# motor_drive_basic.net
KiCad netlist of a schematic drawn in EAGLE
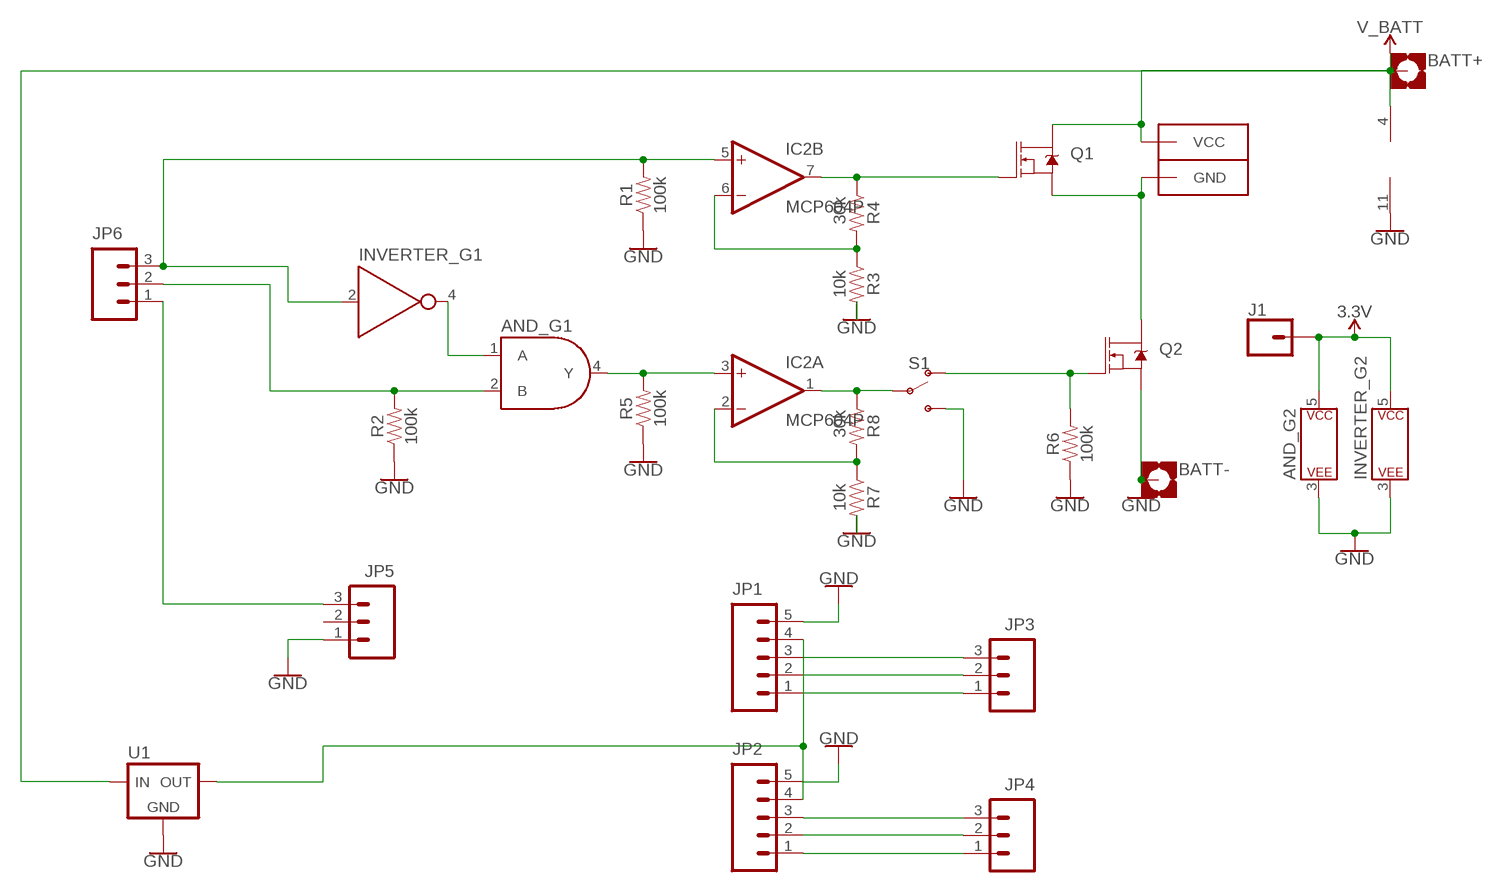
[diagram p0: schematic, sheet 1]

(export (version "E")
  (design (tool "Eeschema 10.0.6"))
  (components
    (comp (ref "AND_")
      (value "74LVC08SE")
      (footprint "eagle-import:SOT23-5")
      (libsource (lib "eagle-import") (part "7408SELVC"))
    )
    (comp (ref "BATT+")
      (value "MOUNT-PAD-SQUARE3.0")
      (footprint "eagle-import:3,0-PAD-SQUARE")
      (libsource (lib "eagle-import") (part "MOUNT-PAD-SQUARE3.0"))
    )
    (comp (ref "BATT-")
      (value "MOUNT-PAD-SQUARE3.0")
      (footprint "eagle-import:3,0-PAD-SQUARE")
      (libsource (lib "eagle-import") (part "MOUNT-PAD-SQUARE3.0"))
    )
    (comp (ref "CONN1")
      (value "ANDERSON_PP_DOUBLEVERTICAL")
      (footprint "eagle-import:ANDERSON_PP_DOUB_VERT")
      (libsource (lib "eagle-import") (part "ANDERSON_PP_DOUBLEVERTICAL"))
    )
    (comp (ref "IC2")
      (value "MCP604P")
      (footprint "eagle-import:DIL14")
      (libsource (lib "eagle-import") (part "MCP604P"))
    )
    (comp (ref "INVERTER_")
      (value "74HC1G04")
      (footprint "eagle-import:SOT353")
      (libsource (lib "eagle-import") (part "741G04HC"))
    )
    (comp (ref "J1")
      (value "CONN_01")
      (footprint "eagle-import:1X01")
      (libsource (lib "eagle-import") (part "CONN_01"))
    )
    (comp (ref "JP1")
      (value "M05PTH")
      (footprint "eagle-import:1X05")
      (libsource (lib "eagle-import") (part "M05PTH"))
    )
    (comp (ref "JP2")
      (value "M05PTH")
      (footprint "eagle-import:1X05")
      (libsource (lib "eagle-import") (part "M05PTH"))
    )
    (comp (ref "JP3")
      (value "M03PTH")
      (footprint "eagle-import:1X03")
      (libsource (lib "eagle-import") (part "M03PTH"))
    )
    (comp (ref "JP4")
      (value "M03PTH")
      (footprint "eagle-import:1X03")
      (libsource (lib "eagle-import") (part "M03PTH"))
    )
    (comp (ref "JP5")
      (value "M03PTH")
      (footprint "eagle-import:1X03")
      (libsource (lib "eagle-import") (part "M03PTH"))
    )
    (comp (ref "JP6")
      (value "M03PTH")
      (footprint "eagle-import:1X03")
      (libsource (lib "eagle-import") (part "M03PTH"))
    )
    (comp (ref "Q1")
      (value "MOSFET-NCH-FQP30N06L")
      (footprint "eagle-import:TO220V")
      (libsource (lib "eagle-import") (part "MOSFET-NCH-FQP30N06L"))
    )
    (comp (ref "Q2")
      (value "MOSFET-NCH-FQP30N06L")
      (footprint "eagle-import:TO220V")
      (libsource (lib "eagle-import") (part "MOSFET-NCH-FQP30N06L"))
    )
    (comp (ref "R1")
      (value "100k")
      (footprint "eagle-import:AXIAL-0.3")
      (libsource (lib "eagle-import") (part "10KOHM-HORIZ-1/4W-1%"))
    )
    (comp (ref "R2")
      (value "100k")
      (footprint "eagle-import:AXIAL-0.3")
      (libsource (lib "eagle-import") (part "10KOHM-HORIZ-1/4W-1%"))
    )
    (comp (ref "R3")
      (value "10k")
      (footprint "eagle-import:AXIAL-0.3")
      (libsource (lib "eagle-import") (part "10KOHM-HORIZ-1/4W-1%"))
    )
    (comp (ref "R4")
      (value "30k")
      (footprint "eagle-import:AXIAL-0.3")
      (libsource (lib "eagle-import") (part "RESISTORAXIAL-0.3"))
    )
    (comp (ref "R5")
      (value "100k")
      (footprint "eagle-import:AXIAL-0.3")
      (libsource (lib "eagle-import") (part "10KOHM-HORIZ-1/4W-1%"))
    )
    (comp (ref "R6")
      (value "100k")
      (footprint "eagle-import:AXIAL-0.3")
      (libsource (lib "eagle-import") (part "10KOHM-HORIZ-1/4W-1%"))
    )
    (comp (ref "R7")
      (value "10k")
      (footprint "eagle-import:AXIAL-0.3")
      (libsource (lib "eagle-import") (part "10KOHM-HORIZ-1/4W-1%"))
    )
    (comp (ref "R8")
      (value "30k")
      (footprint "eagle-import:AXIAL-0.3")
      (libsource (lib "eagle-import") (part "RESISTORAXIAL-0.3"))
    )
    (comp (ref "S1")
      (value "SWITCH-SPDT-PTH-11.6X4.0MM-KIT")
      (footprint "eagle-import:SWITCH_SPDT_PTH_11.6X4.0MM_KIT")
      (libsource (lib "eagle-import") (part "SWITCH-SPDT-PTH-11.6X4.0MM-KIT"))
    )
    (comp (ref "U1")
      (value "78XX-TO220V")
      (footprint "eagle-import:TO220BV")
      (libsource (lib "eagle-import") (part "78XX-TO220V"))
    )
  )
  (nets
    (net (code "1") (name "3.3V") (class "Default")
      (node (ref "AND_") (pin "5") (pinfunction "P$V+_5") (pintype "bidirectional"))
      (node (ref "INVERTER_") (pin "5") (pinfunction "P$V+_5") (pintype "bidirectional"))
      (node (ref "J1") (pin "1") (pinfunction "1_1") (pintype "passive"))
    )
    (net (code "2") (name "GND") (class "Default")
      (node (ref "AND_") (pin "3") (pinfunction "P$V-_3") (pintype "bidirectional"))
      (node (ref "BATT-") (pin "B3,0") (pinfunction "MOUNT_B3,0") (pintype "passive"))
      (node (ref "IC2") (pin "11") (pinfunction "V-_11") (pintype "power_in"))
      (node (ref "INVERTER_") (pin "3") (pinfunction "P$V-_3") (pintype "bidirectional"))
      (node (ref "JP1") (pin "5") (pinfunction "5_5") (pintype "passive"))
      (node (ref "JP2") (pin "5") (pinfunction "5_5") (pintype "passive"))
      (node (ref "JP5") (pin "1") (pinfunction "1_1") (pintype "passive"))
      (node (ref "Q2") (pin "3") (pinfunction "S_3") (pintype "bidirectional"))
      (node (ref "R1") (pin "P$1") (pinfunction "1_P$1") (pintype "passive"))
      (node (ref "R2") (pin "P$1") (pinfunction "1_P$1") (pintype "passive"))
      (node (ref "R3") (pin "P$2") (pinfunction "2_P$2") (pintype "passive"))
      (node (ref "R5") (pin "P$1") (pinfunction "1_P$1") (pintype "passive"))
      (node (ref "R6") (pin "P$1") (pinfunction "1_P$1") (pintype "passive"))
      (node (ref "R7") (pin "P$2") (pinfunction "2_P$2") (pintype "passive"))
      (node (ref "S1") (pin "3") (pinfunction "S_3") (pintype "passive"))
      (node (ref "U1") (pin "2") (pinfunction "GND_2") (pintype "power_in"))
    )
    (net (code "3") (name "Net-(AND_A-A)") (class "Default")
      (node (ref "AND_") (pin "1") (pinfunction "A_1") (pintype "bidirectional"))
      (node (ref "INVERTER_") (pin "4") (pinfunction "Y_4") (pintype "bidirectional"))
    )
    (net (code "4") (name "Net-(AND_A-B)") (class "Default")
      (node (ref "AND_") (pin "2") (pinfunction "B_2") (pintype "bidirectional"))
      (node (ref "JP6") (pin "2") (pinfunction "2_2") (pintype "passive"))
      (node (ref "R2") (pin "P$2") (pinfunction "2_P$2") (pintype "passive"))
    )
    (net (code "5") (name "Net-(AND_A-Y)") (class "Default")
      (node (ref "AND_") (pin "4") (pinfunction "Y_4") (pintype "bidirectional"))
      (node (ref "IC2") (pin "3") (pinfunction "+IN_3") (pintype "input"))
      (node (ref "R5") (pin "P$2") (pinfunction "2_P$2") (pintype "passive"))
    )
    (net (code "6") (name "Net-(CONN1-GND)") (class "Default")
      (node (ref "CONN1") (pin "PIN1") (pinfunction "GND_PIN1") (pintype "bidirectional"))
      (node (ref "Q1") (pin "3") (pinfunction "S_3") (pintype "bidirectional"))
      (node (ref "Q2") (pin "2") (pinfunction "D_2") (pintype "bidirectional"))
    )
    (net (code "7") (name "Net-(IC2A--IN)") (class "Default")
      (node (ref "IC2") (pin "2") (pinfunction "-IN_2") (pintype "input"))
      (node (ref "R7") (pin "P$1") (pinfunction "1_P$1") (pintype "passive"))
      (node (ref "R8") (pin "P$2") (pinfunction "2_P$2") (pintype "passive"))
    )
    (net (code "8") (name "Net-(IC2A-OUT)") (class "Default")
      (node (ref "IC2") (pin "1") (pinfunction "OUT_1") (pintype "output"))
      (node (ref "R8") (pin "P$1") (pinfunction "1_P$1") (pintype "passive"))
      (node (ref "S1") (pin "2") (pinfunction "P_2") (pintype "passive"))
    )
    (net (code "9") (name "Net-(IC2B-+IN)") (class "Default")
      (node (ref "IC2") (pin "5") (pinfunction "+IN_5") (pintype "input"))
      (node (ref "INVERTER_") (pin "2") (pinfunction "A_2") (pintype "bidirectional"))
      (node (ref "JP6") (pin "3") (pinfunction "3_3") (pintype "passive"))
      (node (ref "R1") (pin "P$2") (pinfunction "2_P$2") (pintype "passive"))
    )
    (net (code "10") (name "Net-(IC2B--IN)") (class "Default")
      (node (ref "IC2") (pin "6") (pinfunction "-IN_6") (pintype "input"))
      (node (ref "R3") (pin "P$1") (pinfunction "1_P$1") (pintype "passive"))
      (node (ref "R4") (pin "P$2") (pinfunction "2_P$2") (pintype "passive"))
    )
    (net (code "11") (name "Net-(IC2B-OUT)") (class "Default")
      (node (ref "IC2") (pin "7") (pinfunction "OUT_7") (pintype "output"))
      (node (ref "Q1") (pin "1") (pinfunction "G_1") (pintype "bidirectional"))
      (node (ref "R4") (pin "P$1") (pinfunction "1_P$1") (pintype "passive"))
    )
    (net (code "12") (name "Net-(JP1-Pad1)") (class "Default")
      (node (ref "JP1") (pin "1") (pinfunction "1_1") (pintype "passive"))
      (node (ref "JP3") (pin "1") (pinfunction "1_1") (pintype "passive"))
    )
    (net (code "13") (name "Net-(JP1-Pad2)") (class "Default")
      (node (ref "JP1") (pin "2") (pinfunction "2_2") (pintype "passive"))
      (node (ref "JP3") (pin "2") (pinfunction "2_2") (pintype "passive"))
    )
    (net (code "14") (name "Net-(JP1-Pad3)") (class "Default")
      (node (ref "JP1") (pin "3") (pinfunction "3_3") (pintype "passive"))
      (node (ref "JP3") (pin "3") (pinfunction "3_3") (pintype "passive"))
    )
    (net (code "15") (name "Net-(JP2-Pad1)") (class "Default")
      (node (ref "JP2") (pin "1") (pinfunction "1_1") (pintype "passive"))
      (node (ref "JP4") (pin "1") (pinfunction "1_1") (pintype "passive"))
    )
    (net (code "16") (name "Net-(JP2-Pad2)") (class "Default")
      (node (ref "JP2") (pin "2") (pinfunction "2_2") (pintype "passive"))
      (node (ref "JP4") (pin "2") (pinfunction "2_2") (pintype "passive"))
    )
    (net (code "17") (name "Net-(JP2-Pad3)") (class "Default")
      (node (ref "JP2") (pin "3") (pinfunction "3_3") (pintype "passive"))
      (node (ref "JP4") (pin "3") (pinfunction "3_3") (pintype "passive"))
    )
    (net (code "18") (name "Net-(JP5-Pad3)") (class "Default")
      (node (ref "JP5") (pin "3") (pinfunction "3_3") (pintype "passive"))
      (node (ref "JP6") (pin "1") (pinfunction "1_1") (pintype "passive"))
    )
    (net (code "19") (name "Net-(Q2-G)") (class "Default")
      (node (ref "Q2") (pin "1") (pinfunction "G_1") (pintype "bidirectional"))
      (node (ref "R6") (pin "P$2") (pinfunction "2_P$2") (pintype "passive"))
      (node (ref "S1") (pin "1") (pinfunction "O_1") (pintype "passive"))
    )
    (net (code "20") (name "Net-(U1-VOUT)") (class "Default")
      (node (ref "JP1") (pin "4") (pinfunction "4_4") (pintype "passive"))
      (node (ref "JP2") (pin "4") (pinfunction "4_4") (pintype "passive"))
      (node (ref "U1") (pin "3") (pinfunction "VOUT_3") (pintype "power_in"))
    )
    (net (code "21") (name "V_BATT") (class "Default")
      (node (ref "BATT+") (pin "B3,0") (pinfunction "MOUNT_B3,0") (pintype "passive"))
      (node (ref "CONN1") (pin "PIN2") (pinfunction "VCC_PIN2") (pintype "bidirectional"))
      (node (ref "IC2") (pin "4") (pinfunction "V+_4") (pintype "power_in"))
      (node (ref "Q1") (pin "2") (pinfunction "D_2") (pintype "bidirectional"))
      (node (ref "U1") (pin "1") (pinfunction "VIN_1") (pintype "power_in"))
    )
    (net (code "22") (name "unconnected-(JP5-Pad2)") (class "Default")
      (node (ref "JP5") (pin "2") (pinfunction "2_2") (pintype "passive"))
    )
  )
)
